# gsm.net
KiCad netlist of a schematic drawn in EAGLE
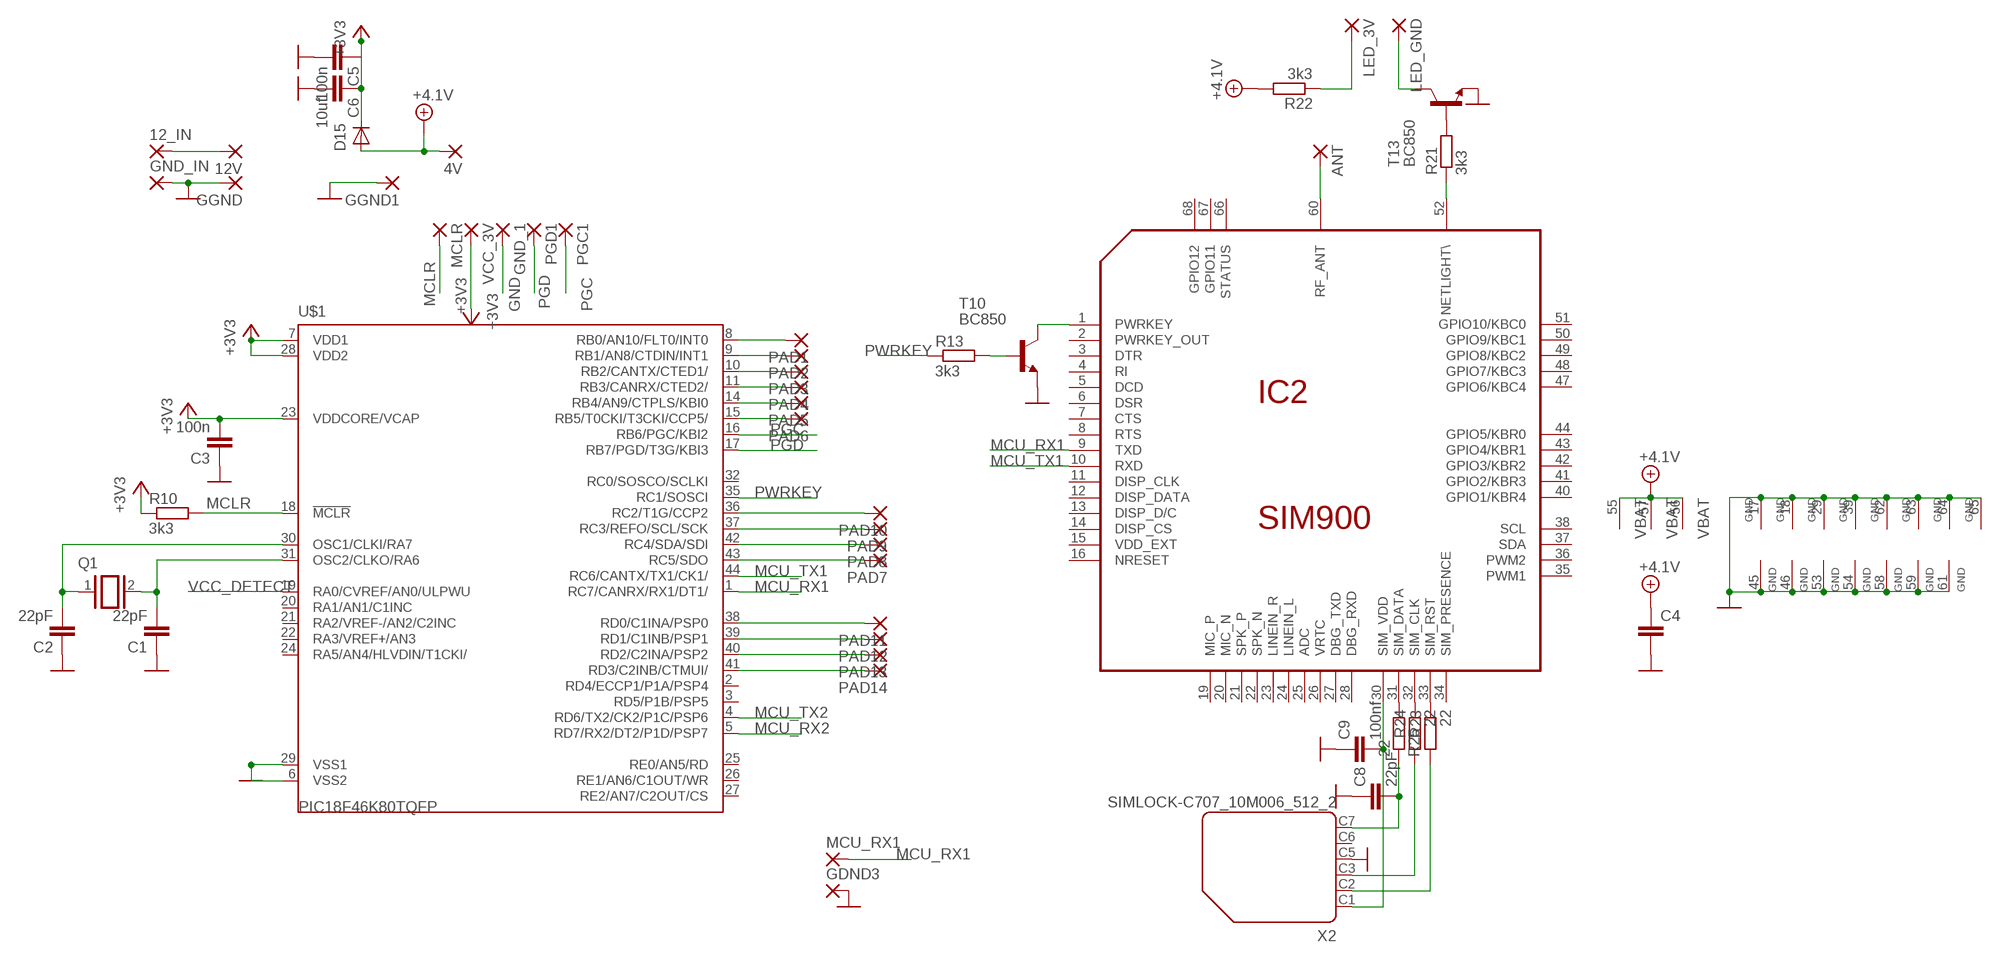
[diagram p0: schematic, sheet 1]

(export (version "E")
  (design (tool "Eeschema 10.0.6"))
  (components
    (comp (ref "4V")
      (value "SMD2")
      (footprint "eagle-import:SMD1,27-2,54")
      (libsource (lib "eagle-import") (part "SMD2"))
    )
    (comp (ref "12V")
      (value "SMD2")
      (footprint "eagle-import:SMD1,27-2,54")
      (libsource (lib "eagle-import") (part "SMD2"))
    )
    (comp (ref "12_IN")
      (value "2,15/1,0")
      (footprint "eagle-import:2,15_1,0")
      (libsource (lib "eagle-import") (part "2,15/1,0"))
    )
    (comp (ref "ANT")
      (value "2,54/0,8")
      (footprint "eagle-import:2,54_0,8")
      (libsource (lib "eagle-import") (part "2,54/0,8"))
    )
    (comp (ref "C1")
      (value "22pF")
      (footprint "eagle-import:C1206")
      (libsource (lib "eagle-import") (part "resistor_C-EUC1206"))
    )
    (comp (ref "C2")
      (value "22pF")
      (footprint "eagle-import:C1206")
      (libsource (lib "eagle-import") (part "resistor_C-EUC1206"))
    )
    (comp (ref "C3")
      (value "100n")
      (footprint "eagle-import:C1206")
      (libsource (lib "eagle-import") (part "resistor_C-EUC1206"))
    )
    (comp (ref "C4")
      (value "C-EU025-050X050")
      (footprint "eagle-import:C025-050X050")
      (libsource (lib "eagle-import") (part "C-EU025-050X050"))
    )
    (comp (ref "C5")
      (value "100n")
      (footprint "eagle-import:C1206")
      (libsource (lib "eagle-import") (part "resistor_C-EUC1206"))
    )
    (comp (ref "C6")
      (value "10uf")
      (footprint "eagle-import:C1206")
      (libsource (lib "eagle-import") (part "resistor_C-EUC1206"))
    )
    (comp (ref "C8")
      (value "22pF")
      (footprint "eagle-import:C1206K")
      (libsource (lib "eagle-import") (part "C-EUC1206K"))
    )
    (comp (ref "C9")
      (value "100nf")
      (footprint "eagle-import:C1206K")
      (libsource (lib "eagle-import") (part "C-EUC1206K"))
    )
    (comp (ref "D15")
      (value "GF1")
      (footprint "eagle-import:SMA-DO214AC")
      (libsource (lib "eagle-import") (part "GF1"))
    )
    (comp (ref "GDND3")
      (value "2,15/1,0")
      (footprint "eagle-import:2,15_1,0")
      (libsource (lib "eagle-import") (part "2,15/1,0"))
    )
    (comp (ref "GGND")
      (value "SMD2")
      (footprint "eagle-import:SMD1,27-2,54")
      (libsource (lib "eagle-import") (part "SMD2"))
    )
    (comp (ref "GGND1")
      (value "SMD2")
      (footprint "eagle-import:SMD1,27-2,54")
      (libsource (lib "eagle-import") (part "SMD2"))
    )
    (comp (ref "GND_1")
      (value "2,15/1,0")
      (footprint "eagle-import:2,15_1,0")
      (libsource (lib "eagle-import") (part "2,15/1,0"))
    )
    (comp (ref "GND_IN")
      (value "2,15/1,0")
      (footprint "eagle-import:2,15_1,0")
      (libsource (lib "eagle-import") (part "2,15/1,0"))
    )
    (comp (ref "IC2")
      (value "SIM900")
      (footprint "eagle-import:SIM900")
      (libsource (lib "eagle-import") (part "SIM900"))
    )
    (comp (ref "LED_3V")
      (value "WIREPAD2,15/1,0")
      (footprint "eagle-import:2,15_1,0")
      (libsource (lib "eagle-import") (part "WIREPAD2,15/1,0"))
    )
    (comp (ref "LED_GND")
      (value "WIREPAD2,15/1,0")
      (footprint "eagle-import:2,15_1,0")
      (libsource (lib "eagle-import") (part "WIREPAD2,15/1,0"))
    )
    (comp (ref "MCLR")
      (value "2,15/1,0")
      (footprint "eagle-import:2,15_1,0")
      (libsource (lib "eagle-import") (part "2,15/1,0"))
    )
    (comp (ref "MCU_RX1")
      (value "2,15/1,0")
      (footprint "eagle-import:2,15_1,0")
      (libsource (lib "eagle-import") (part "2,15/1,0"))
    )
    (comp (ref "PAD1")
      (value "SMD2")
      (footprint "eagle-import:SMD1,27-2,54")
      (libsource (lib "eagle-import") (part "SMD2"))
    )
    (comp (ref "PAD2")
      (value "SMD2")
      (footprint "eagle-import:SMD1,27-2,54")
      (libsource (lib "eagle-import") (part "SMD2"))
    )
    (comp (ref "PAD3")
      (value "SMD2")
      (footprint "eagle-import:SMD1,27-2,54")
      (libsource (lib "eagle-import") (part "SMD2"))
    )
    (comp (ref "PAD4")
      (value "SMD2")
      (footprint "eagle-import:SMD1,27-2,54")
      (libsource (lib "eagle-import") (part "SMD2"))
    )
    (comp (ref "PAD5")
      (value "SMD2")
      (footprint "eagle-import:SMD1,27-2,54")
      (libsource (lib "eagle-import") (part "SMD2"))
    )
    (comp (ref "PAD6")
      (value "SMD2")
      (footprint "eagle-import:SMD1,27-2,54")
      (libsource (lib "eagle-import") (part "SMD2"))
    )
    (comp (ref "PAD7")
      (value "SMD2")
      (footprint "eagle-import:SMD1,27-2,54")
      (libsource (lib "eagle-import") (part "SMD2"))
    )
    (comp (ref "PAD8")
      (value "SMD2")
      (footprint "eagle-import:SMD1,27-2,54")
      (libsource (lib "eagle-import") (part "SMD2"))
    )
    (comp (ref "PAD9")
      (value "SMD2")
      (footprint "eagle-import:SMD1,27-2,54")
      (libsource (lib "eagle-import") (part "SMD2"))
    )
    (comp (ref "PAD10")
      (value "SMD2")
      (footprint "eagle-import:SMD1,27-2,54")
      (libsource (lib "eagle-import") (part "SMD2"))
    )
    (comp (ref "PAD11")
      (value "SMD2")
      (footprint "eagle-import:SMD1,27-2,54")
      (libsource (lib "eagle-import") (part "SMD2"))
    )
    (comp (ref "PAD12")
      (value "SMD2")
      (footprint "eagle-import:SMD1,27-2,54")
      (libsource (lib "eagle-import") (part "SMD2"))
    )
    (comp (ref "PAD13")
      (value "SMD2")
      (footprint "eagle-import:SMD1,27-2,54")
      (libsource (lib "eagle-import") (part "SMD2"))
    )
    (comp (ref "PAD14")
      (value "SMD2")
      (footprint "eagle-import:SMD1,27-2,54")
      (libsource (lib "eagle-import") (part "SMD2"))
    )
    (comp (ref "PGC1")
      (value "2,15/1,0")
      (footprint "eagle-import:2,15_1,0")
      (libsource (lib "eagle-import") (part "2,15/1,0"))
    )
    (comp (ref "PGD1")
      (value "2,15/1,0")
      (footprint "eagle-import:2,15_1,0")
      (libsource (lib "eagle-import") (part "2,15/1,0"))
    )
    (comp (ref "Q1")
      (value "XTAL/S")
      (footprint "eagle-import:QS")
      (libsource (lib "eagle-import") (part "XTAL/S"))
    )
    (comp (ref "R10")
      (value "3k3")
      (footprint "eagle-import:M3216")
      (libsource (lib "eagle-import") (part "R-EU_M3216"))
    )
    (comp (ref "R13")
      (value "3k3")
      (footprint "eagle-import:M3216")
      (libsource (lib "eagle-import") (part "R-EU_M3216"))
    )
    (comp (ref "R21")
      (value "3k3")
      (footprint "eagle-import:M3216")
      (libsource (lib "eagle-import") (part "R-EU_M3216"))
    )
    (comp (ref "R22")
      (value "3k3")
      (footprint "eagle-import:M3216")
      (libsource (lib "eagle-import") (part "R-EU_M3216"))
    )
    (comp (ref "R23")
      (value "22")
      (footprint "eagle-import:M1206")
      (libsource (lib "eagle-import") (part "resistor_R-EU_M1206"))
    )
    (comp (ref "R24")
      (value "22")
      (footprint "eagle-import:M1206")
      (libsource (lib "eagle-import") (part "resistor_R-EU_M1206"))
    )
    (comp (ref "R25")
      (value "22")
      (footprint "eagle-import:M1206")
      (libsource (lib "eagle-import") (part "resistor_R-EU_M1206"))
    )
    (comp (ref "T10")
      (value "BC850")
      (footprint "eagle-import:SOT23")
      (libsource (lib "eagle-import") (part "BC850"))
    )
    (comp (ref "T13")
      (value "BC850")
      (footprint "eagle-import:SOT23")
      (libsource (lib "eagle-import") (part "BC850"))
    )
    (comp (ref "U$1")
      (value "PIC18F46K80TQFP")
      (footprint "eagle-import:TQFP44")
      (libsource (lib "eagle-import") (part "PIC18F46K80TQFP"))
    )
    (comp (ref "VCC_3V")
      (value "2,15/1,0")
      (footprint "eagle-import:2,15_1,0")
      (libsource (lib "eagle-import") (part "2,15/1,0"))
    )
    (comp (ref "X2")
      (value "SIMLOCK-C707_10M006_512_2")
      (footprint "eagle-import:C707_10M006_512_2")
      (libsource (lib "eagle-import") (part "SIMLOCK-C707_10M006_512_2"))
    )
  )
  (nets
    (net (code "1") (name "+3V3") (class "Default")
      (node (ref "C3") (pin "2") (pinfunction "2_2") (pintype "passive"))
      (node (ref "C5") (pin "1") (pinfunction "1_1") (pintype "passive"))
      (node (ref "C6") (pin "1") (pinfunction "1_1") (pintype "passive"))
      (node (ref "D15") (pin "K") (pinfunction "C_K") (pintype "passive"))
      (node (ref "R10") (pin "1") (pinfunction "1_1") (pintype "passive"))
      (node (ref "U$1") (pin "23") (pinfunction "VDDCORE/VCAP_23") (pintype "input"))
      (node (ref "U$1") (pin "28") (pinfunction "VDD2_28") (pintype "input"))
      (node (ref "U$1") (pin "7") (pinfunction "VDD1_7") (pintype "input"))
      (node (ref "VCC_3V") (pin "1") (pinfunction "P_1") (pintype "passive"))
    )
    (net (code "2") (name "+4.1V") (class "Default")
      (node (ref "4V") (pin "1") (pinfunction "P_1") (pintype "passive"))
      (node (ref "C4") (pin "1") (pinfunction "1_1") (pintype "passive"))
      (node (ref "D15") (pin "A") (pinfunction "A_A") (pintype "passive"))
      (node (ref "IC2") (pin "55") (pinfunction "VBAT_55") (pintype "power_in"))
      (node (ref "IC2") (pin "56") (pinfunction "VBAT_56") (pintype "power_in"))
      (node (ref "IC2") (pin "57") (pinfunction "VBAT_57") (pintype "power_in"))
      (node (ref "R22") (pin "2") (pinfunction "2_2") (pintype "passive"))
    )
    (net (code "3") (name "/MCLR") (class "Default")
      (node (ref "MCLR") (pin "1") (pinfunction "P_1") (pintype "passive"))
      (node (ref "R10") (pin "2") (pinfunction "2_2") (pintype "passive"))
      (node (ref "U$1") (pin "18") (pinfunction "~{MCLR}_18") (pintype "input"))
    )
    (net (code "4") (name "/MCU_RX1") (class "Default")
      (node (ref "IC2") (pin "9") (pinfunction "TXD_9") (pintype "bidirectional"))
      (node (ref "MCU_RX1") (pin "1") (pinfunction "P_1") (pintype "passive"))
      (node (ref "U$1") (pin "1") (pinfunction "RC7/CANRX/RX1/DT1/_1") (pintype "bidirectional"))
    )
    (net (code "5") (name "/MCU_RX2") (class "Default")
      (node (ref "U$1") (pin "5") (pinfunction "RD7/RX2/DT2/P1D/PSP7_5") (pintype "bidirectional"))
    )
    (net (code "6") (name "/MCU_TX1") (class "Default")
      (node (ref "IC2") (pin "10") (pinfunction "RXD_10") (pintype "bidirectional"))
      (node (ref "U$1") (pin "44") (pinfunction "RC6/CANTX/TX1/CK1/_44") (pintype "bidirectional"))
    )
    (net (code "7") (name "/MCU_TX2") (class "Default")
      (node (ref "U$1") (pin "4") (pinfunction "RD6/TX2/CK2/P1C/PSP6_4") (pintype "bidirectional"))
    )
    (net (code "8") (name "/PGC") (class "Default")
      (node (ref "PGC1") (pin "1") (pinfunction "P_1") (pintype "passive"))
      (node (ref "U$1") (pin "16") (pinfunction "RB6/PGC/KBI2_16") (pintype "bidirectional"))
    )
    (net (code "9") (name "/PGD") (class "Default")
      (node (ref "PGD1") (pin "1") (pinfunction "P_1") (pintype "passive"))
      (node (ref "U$1") (pin "17") (pinfunction "RB7/PGD/T3G/KBI3_17") (pintype "bidirectional"))
    )
    (net (code "10") (name "/PWRKEY") (class "Default")
      (node (ref "R13") (pin "1") (pinfunction "1_1") (pintype "passive"))
      (node (ref "U$1") (pin "35") (pinfunction "RC1/SOSCI_35") (pintype "bidirectional"))
    )
    (net (code "11") (name "/VCC_DETECT") (class "Default")
      (node (ref "U$1") (pin "19") (pinfunction "RA0/CVREF/AN0/ULPWU_19") (pintype "bidirectional"))
    )
    (net (code "12") (name "GND") (class "Default")
      (node (ref "C1") (pin "1") (pinfunction "1_1") (pintype "passive"))
      (node (ref "C2") (pin "1") (pinfunction "1_1") (pintype "passive"))
      (node (ref "C3") (pin "1") (pinfunction "1_1") (pintype "passive"))
      (node (ref "C4") (pin "2") (pinfunction "2_2") (pintype "passive"))
      (node (ref "C5") (pin "2") (pinfunction "2_2") (pintype "passive"))
      (node (ref "C6") (pin "2") (pinfunction "2_2") (pintype "passive"))
      (node (ref "C8") (pin "1") (pinfunction "1_1") (pintype "passive"))
      (node (ref "C9") (pin "1") (pinfunction "1_1") (pintype "passive"))
      (node (ref "GDND3") (pin "1") (pinfunction "P_1") (pintype "passive"))
      (node (ref "GGND") (pin "1") (pinfunction "P_1") (pintype "passive"))
      (node (ref "GGND1") (pin "1") (pinfunction "P_1") (pintype "passive"))
      (node (ref "GND_1") (pin "1") (pinfunction "P_1") (pintype "passive"))
      (node (ref "GND_IN") (pin "1") (pinfunction "P_1") (pintype "passive"))
      (node (ref "IC2") (pin "17") (pinfunction "GND_17") (pintype "power_in"))
      (node (ref "IC2") (pin "18") (pinfunction "GND_18") (pintype "power_in"))
      (node (ref "IC2") (pin "29") (pinfunction "GND_29") (pintype "power_in"))
      (node (ref "IC2") (pin "39") (pinfunction "GND_39") (pintype "power_in"))
      (node (ref "IC2") (pin "45") (pinfunction "GND_45") (pintype "power_in"))
      (node (ref "IC2") (pin "46") (pinfunction "GND_46") (pintype "power_in"))
      (node (ref "IC2") (pin "53") (pinfunction "GND_53") (pintype "power_in"))
      (node (ref "IC2") (pin "54") (pinfunction "GND_54") (pintype "power_in"))
      (node (ref "IC2") (pin "58") (pinfunction "GND_58") (pintype "power_in"))
      (node (ref "IC2") (pin "59") (pinfunction "GND_59") (pintype "power_in"))
      (node (ref "IC2") (pin "61") (pinfunction "GND_61") (pintype "power_in"))
      (node (ref "IC2") (pin "62") (pinfunction "GND_62") (pintype "power_in"))
      (node (ref "IC2") (pin "63") (pinfunction "GND_63") (pintype "power_in"))
      (node (ref "IC2") (pin "64") (pinfunction "GND_64") (pintype "power_in"))
      (node (ref "IC2") (pin "65") (pinfunction "GND_65") (pintype "power_in"))
      (node (ref "T10") (pin "2") (pinfunction "E_2") (pintype "passive"))
      (node (ref "T13") (pin "2") (pinfunction "E_2") (pintype "passive"))
      (node (ref "U$1") (pin "29") (pinfunction "VSS1_29") (pintype "input"))
      (node (ref "U$1") (pin "6") (pinfunction "VSS2_6") (pintype "input"))
      (node (ref "X2") (pin "C5") (pinfunction "4_C5") (pintype "passive"))
    )
    (net (code "13") (name "Net-(12V-P)") (class "Default")
      (node (ref "12V") (pin "1") (pinfunction "P_1") (pintype "passive"))
      (node (ref "12_IN") (pin "1") (pinfunction "P_1") (pintype "passive"))
    )
    (net (code "14") (name "Net-(ANT-P)") (class "Default")
      (node (ref "ANT") (pin "1") (pinfunction "P_1") (pintype "passive"))
      (node (ref "IC2") (pin "60") (pinfunction "RF_ANT_60") (pintype "bidirectional"))
    )
    (net (code "15") (name "Net-(IC2A-NETLIGHT\\)") (class "Default")
      (node (ref "IC2") (pin "52") (pinfunction "NETLIGHT\\_52") (pintype "bidirectional"))
      (node (ref "R21") (pin "1") (pinfunction "1_1") (pintype "passive"))
    )
    (net (code "16") (name "Net-(IC2A-PWRKEY)") (class "Default")
      (node (ref "IC2") (pin "1") (pinfunction "PWRKEY_1") (pintype "bidirectional"))
      (node (ref "T10") (pin "3") (pinfunction "C_3") (pintype "passive"))
    )
    (net (code "17") (name "Net-(IC2A-SIM_CLK)") (class "Default")
      (node (ref "IC2") (pin "32") (pinfunction "SIM_CLK_32") (pintype "bidirectional"))
      (node (ref "R24") (pin "1") (pinfunction "1_1") (pintype "passive"))
    )
    (net (code "18") (name "Net-(IC2A-SIM_DATA)") (class "Default")
      (node (ref "IC2") (pin "31") (pinfunction "SIM_DATA_31") (pintype "bidirectional"))
      (node (ref "R25") (pin "2") (pinfunction "2_2") (pintype "passive"))
    )
    (net (code "19") (name "Net-(IC2A-SIM_RST)") (class "Default")
      (node (ref "IC2") (pin "33") (pinfunction "SIM_RST_33") (pintype "bidirectional"))
      (node (ref "R23") (pin "1") (pinfunction "1_1") (pintype "passive"))
    )
    (net (code "20") (name "Net-(IC2A-SIM_VDD)") (class "Default")
      (node (ref "C9") (pin "2") (pinfunction "2_2") (pintype "passive"))
      (node (ref "IC2") (pin "30") (pinfunction "SIM_VDD_30") (pintype "bidirectional"))
      (node (ref "X2") (pin "C1") (pinfunction "1_C1") (pintype "passive"))
    )
    (net (code "21") (name "Net-(LED_3V-P)") (class "Default")
      (node (ref "LED_3V") (pin "1") (pinfunction "P_1") (pintype "passive"))
      (node (ref "R22") (pin "1") (pinfunction "1_1") (pintype "passive"))
    )
    (net (code "22") (name "Net-(LED_GND-P)") (class "Default")
      (node (ref "LED_GND") (pin "1") (pinfunction "P_1") (pintype "passive"))
      (node (ref "T13") (pin "3") (pinfunction "C_3") (pintype "passive"))
    )
    (net (code "23") (name "Net-(PAD1-P)") (class "Default")
      (node (ref "PAD1") (pin "1") (pinfunction "P_1") (pintype "passive"))
      (node (ref "U$1") (pin "8") (pinfunction "RB0/AN10/FLT0/INT0_8") (pintype "bidirectional"))
    )
    (net (code "24") (name "Net-(PAD2-P)") (class "Default")
      (node (ref "PAD2") (pin "1") (pinfunction "P_1") (pintype "passive"))
      (node (ref "U$1") (pin "9") (pinfunction "RB1/AN8/CTDIN/INT1_9") (pintype "bidirectional"))
    )
    (net (code "25") (name "Net-(PAD3-P)") (class "Default")
      (node (ref "PAD3") (pin "1") (pinfunction "P_1") (pintype "passive"))
      (node (ref "U$1") (pin "10") (pinfunction "RB2/CANTX/CTED1/_10") (pintype "bidirectional"))
    )
    (net (code "26") (name "Net-(PAD4-P)") (class "Default")
      (node (ref "PAD4") (pin "1") (pinfunction "P_1") (pintype "passive"))
      (node (ref "U$1") (pin "11") (pinfunction "RB3/CANRX/CTED2/_11") (pintype "bidirectional"))
    )
    (net (code "27") (name "Net-(PAD5-P)") (class "Default")
      (node (ref "PAD5") (pin "1") (pinfunction "P_1") (pintype "passive"))
      (node (ref "U$1") (pin "14") (pinfunction "RB4/AN9/CTPLS/KBI0_14") (pintype "bidirectional"))
    )
    (net (code "28") (name "Net-(PAD6-P)") (class "Default")
      (node (ref "PAD6") (pin "1") (pinfunction "P_1") (pintype "passive"))
      (node (ref "U$1") (pin "15") (pinfunction "RB5/T0CKI/T3CKI/CCP5/_15") (pintype "bidirectional"))
    )
    (net (code "29") (name "Net-(PAD7-P)") (class "Default")
      (node (ref "PAD7") (pin "1") (pinfunction "P_1") (pintype "passive"))
      (node (ref "U$1") (pin "43") (pinfunction "RC5/SDO_43") (pintype "bidirectional"))
    )
    (net (code "30") (name "Net-(PAD8-P)") (class "Default")
      (node (ref "PAD8") (pin "1") (pinfunction "P_1") (pintype "passive"))
      (node (ref "U$1") (pin "42") (pinfunction "RC4/SDA/SDI_42") (pintype "bidirectional"))
    )
    (net (code "31") (name "Net-(PAD9-P)") (class "Default")
      (node (ref "PAD9") (pin "1") (pinfunction "P_1") (pintype "passive"))
      (node (ref "U$1") (pin "37") (pinfunction "RC3/REFO/SCL/SCK_37") (pintype "input"))
    )
    (net (code "32") (name "Net-(PAD10-P)") (class "Default")
      (node (ref "PAD10") (pin "1") (pinfunction "P_1") (pintype "passive"))
      (node (ref "U$1") (pin "36") (pinfunction "RC2/T1G/CCP2_36") (pintype "bidirectional"))
    )
    (net (code "33") (name "Net-(PAD11-P)") (class "Default")
      (node (ref "PAD11") (pin "1") (pinfunction "P_1") (pintype "passive"))
      (node (ref "U$1") (pin "38") (pinfunction "RD0/C1INA/PSP0_38") (pintype "bidirectional"))
    )
    (net (code "34") (name "Net-(PAD12-P)") (class "Default")
      (node (ref "PAD12") (pin "1") (pinfunction "P_1") (pintype "passive"))
      (node (ref "U$1") (pin "39") (pinfunction "RD1/C1INB/PSP1_39") (pintype "bidirectional"))
    )
    (net (code "35") (name "Net-(PAD13-P)") (class "Default")
      (node (ref "PAD13") (pin "1") (pinfunction "P_1") (pintype "passive"))
      (node (ref "U$1") (pin "40") (pinfunction "RD2/C2INA/PSP2_40") (pintype "bidirectional"))
    )
    (net (code "36") (name "Net-(PAD14-P)") (class "Default")
      (node (ref "PAD14") (pin "1") (pinfunction "P_1") (pintype "passive"))
      (node (ref "U$1") (pin "41") (pinfunction "RD3/C2INB/CTMUI/_41") (pintype "bidirectional"))
    )
    (net (code "37") (name "Net-(T10-B)") (class "Default")
      (node (ref "R13") (pin "2") (pinfunction "2_2") (pintype "passive"))
      (node (ref "T10") (pin "1") (pinfunction "B_1") (pintype "passive"))
    )
    (net (code "38") (name "Net-(T13-B)") (class "Default")
      (node (ref "R21") (pin "2") (pinfunction "2_2") (pintype "passive"))
      (node (ref "T13") (pin "1") (pinfunction "B_1") (pintype "passive"))
    )
    (net (code "39") (name "Net-(U$1-OSC1{slash}CLKI{slash}RA7)") (class "Default")
      (node (ref "C2") (pin "2") (pinfunction "2_2") (pintype "passive"))
      (node (ref "Q1") (pin "1") (pinfunction "1_1") (pintype "passive"))
      (node (ref "U$1") (pin "30") (pinfunction "OSC1/CLKI/RA7_30") (pintype "bidirectional"))
    )
    (net (code "40") (name "Net-(U$1-OSC2{slash}CLKO{slash}RA6)") (class "Default")
      (node (ref "C1") (pin "2") (pinfunction "2_2") (pintype "passive"))
      (node (ref "Q1") (pin "2") (pinfunction "2_2") (pintype "passive"))
      (node (ref "U$1") (pin "31") (pinfunction "OSC2/CLKO/RA6_31") (pintype "bidirectional"))
    )
    (net (code "41") (name "Net-(X2-2)") (class "Default")
      (node (ref "R23") (pin "2") (pinfunction "2_2") (pintype "passive"))
      (node (ref "X2") (pin "C2") (pinfunction "2_C2") (pintype "passive"))
    )
    (net (code "42") (name "Net-(X2-3)") (class "Default")
      (node (ref "R24") (pin "2") (pinfunction "2_2") (pintype "passive"))
      (node (ref "X2") (pin "C3") (pinfunction "3_C3") (pintype "passive"))
    )
    (net (code "43") (name "Net-(X2-6)") (class "Default")
      (node (ref "C8") (pin "2") (pinfunction "2_2") (pintype "passive"))
      (node (ref "R25") (pin "1") (pinfunction "1_1") (pintype "passive"))
      (node (ref "X2") (pin "C7") (pinfunction "6_C7") (pintype "passive"))
    )
    (net (code "44") (name "unconnected-(IC2A-ADC-Pad25)") (class "Default")
      (node (ref "IC2") (pin "25") (pinfunction "ADC_25") (pintype "bidirectional"))
    )
    (net (code "45") (name "unconnected-(IC2A-CTS-Pad7)") (class "Default")
      (node (ref "IC2") (pin "7") (pinfunction "CTS_7") (pintype "bidirectional"))
    )
    (net (code "46") (name "unconnected-(IC2A-DBG_RXD-Pad28)") (class "Default")
      (node (ref "IC2") (pin "28") (pinfunction "DBG_RXD_28") (pintype "bidirectional"))
    )
    (net (code "47") (name "unconnected-(IC2A-DBG_TXD-Pad27)") (class "Default")
      (node (ref "IC2") (pin "27") (pinfunction "DBG_TXD_27") (pintype "bidirectional"))
    )
    (net (code "48") (name "unconnected-(IC2A-DCD-Pad5)") (class "Default")
      (node (ref "IC2") (pin "5") (pinfunction "DCD_5") (pintype "bidirectional"))
    )
    (net (code "49") (name "unconnected-(IC2A-DISP_CLK-Pad11)") (class "Default")
      (node (ref "IC2") (pin "11") (pinfunction "DISP_CLK_11") (pintype "bidirectional"))
    )
    (net (code "50") (name "unconnected-(IC2A-DISP_CS-Pad14)") (class "Default")
      (node (ref "IC2") (pin "14") (pinfunction "DISP_CS_14") (pintype "bidirectional"))
    )
    (net (code "51") (name "unconnected-(IC2A-DISP_DATA-Pad12)") (class "Default")
      (node (ref "IC2") (pin "12") (pinfunction "DISP_DATA_12") (pintype "bidirectional"))
    )
    (net (code "52") (name "unconnected-(IC2A-DISP_D{slash}C-Pad13)") (class "Default")
      (node (ref "IC2") (pin "13") (pinfunction "DISP_D/C_13") (pintype "bidirectional"))
    )
    (net (code "53") (name "unconnected-(IC2A-DSR-Pad6)") (class "Default")
      (node (ref "IC2") (pin "6") (pinfunction "DSR_6") (pintype "bidirectional"))
    )
    (net (code "54") (name "unconnected-(IC2A-DTR-Pad3)") (class "Default")
      (node (ref "IC2") (pin "3") (pinfunction "DTR_3") (pintype "bidirectional"))
    )
    (net (code "55") (name "unconnected-(IC2A-GPIO1{slash}KBR4-Pad40)") (class "Default")
      (node (ref "IC2") (pin "40") (pinfunction "GPIO1/KBR4_40") (pintype "bidirectional"))
    )
    (net (code "56") (name "unconnected-(IC2A-GPIO2{slash}KBR3-Pad41)") (class "Default")
      (node (ref "IC2") (pin "41") (pinfunction "GPIO2/KBR3_41") (pintype "bidirectional"))
    )
    (net (code "57") (name "unconnected-(IC2A-GPIO3{slash}KBR2-Pad42)") (class "Default")
      (node (ref "IC2") (pin "42") (pinfunction "GPIO3/KBR2_42") (pintype "bidirectional"))
    )
    (net (code "58") (name "unconnected-(IC2A-GPIO4{slash}KBR1-Pad43)") (class "Default")
      (node (ref "IC2") (pin "43") (pinfunction "GPIO4/KBR1_43") (pintype "bidirectional"))
    )
    (net (code "59") (name "unconnected-(IC2A-GPIO5{slash}KBR0-Pad44)") (class "Default")
      (node (ref "IC2") (pin "44") (pinfunction "GPIO5/KBR0_44") (pintype "bidirectional"))
    )
    (net (code "60") (name "unconnected-(IC2A-GPIO6{slash}KBC4-Pad47)") (class "Default")
      (node (ref "IC2") (pin "47") (pinfunction "GPIO6/KBC4_47") (pintype "bidirectional"))
    )
    (net (code "61") (name "unconnected-(IC2A-GPIO7{slash}KBC3-Pad48)") (class "Default")
      (node (ref "IC2") (pin "48") (pinfunction "GPIO7/KBC3_48") (pintype "bidirectional"))
    )
    (net (code "62") (name "unconnected-(IC2A-GPIO8{slash}KBC2-Pad49)") (class "Default")
      (node (ref "IC2") (pin "49") (pinfunction "GPIO8/KBC2_49") (pintype "bidirectional"))
    )
    (net (code "63") (name "unconnected-(IC2A-GPIO9{slash}KBC1-Pad50)") (class "Default")
      (node (ref "IC2") (pin "50") (pinfunction "GPIO9/KBC1_50") (pintype "bidirectional"))
    )
    (net (code "64") (name "unconnected-(IC2A-GPIO10{slash}KBC0-Pad51)") (class "Default")
      (node (ref "IC2") (pin "51") (pinfunction "GPIO10/KBC0_51") (pintype "bidirectional"))
    )
    (net (code "65") (name "unconnected-(IC2A-GPIO11-Pad67)") (class "Default")
      (node (ref "IC2") (pin "67") (pinfunction "GPIO11_67") (pintype "bidirectional"))
    )
    (net (code "66") (name "unconnected-(IC2A-GPIO12-Pad68)") (class "Default")
      (node (ref "IC2") (pin "68") (pinfunction "GPIO12_68") (pintype "bidirectional"))
    )
    (net (code "67") (name "unconnected-(IC2A-LINEIN_L-Pad24)") (class "Default")
      (node (ref "IC2") (pin "24") (pinfunction "LINEIN_L_24") (pintype "bidirectional"))
    )
    (net (code "68") (name "unconnected-(IC2A-LINEIN_R-Pad23)") (class "Default")
      (node (ref "IC2") (pin "23") (pinfunction "LINEIN_R_23") (pintype "bidirectional"))
    )
    (net (code "69") (name "unconnected-(IC2A-MIC_N-Pad20)") (class "Default")
      (node (ref "IC2") (pin "20") (pinfunction "MIC_N_20") (pintype "bidirectional"))
    )
    (net (code "70") (name "unconnected-(IC2A-MIC_P-Pad19)") (class "Default")
      (node (ref "IC2") (pin "19") (pinfunction "MIC_P_19") (pintype "bidirectional"))
    )
    (net (code "71") (name "unconnected-(IC2A-NRESET-Pad16)") (class "Default")
      (node (ref "IC2") (pin "16") (pinfunction "NRESET_16") (pintype "bidirectional"))
    )
    (net (code "72") (name "unconnected-(IC2A-PWM1-Pad35)") (class "Default")
      (node (ref "IC2") (pin "35") (pinfunction "PWM1_35") (pintype "bidirectional"))
    )
    (net (code "73") (name "unconnected-(IC2A-PWM2-Pad36)") (class "Default")
      (node (ref "IC2") (pin "36") (pinfunction "PWM2_36") (pintype "bidirectional"))
    )
    (net (code "74") (name "unconnected-(IC2A-PWRKEY_OUT-Pad2)") (class "Default")
      (node (ref "IC2") (pin "2") (pinfunction "PWRKEY_OUT_2") (pintype "bidirectional"))
    )
    (net (code "75") (name "unconnected-(IC2A-RI-Pad4)") (class "Default")
      (node (ref "IC2") (pin "4") (pinfunction "RI_4") (pintype "bidirectional"))
    )
    (net (code "76") (name "unconnected-(IC2A-RTS-Pad8)") (class "Default")
      (node (ref "IC2") (pin "8") (pinfunction "RTS_8") (pintype "bidirectional"))
    )
    (net (code "77") (name "unconnected-(IC2A-SCL-Pad38)") (class "Default")
      (node (ref "IC2") (pin "38") (pinfunction "SCL_38") (pintype "bidirectional"))
    )
    (net (code "78") (name "unconnected-(IC2A-SDA-Pad37)") (class "Default")
      (node (ref "IC2") (pin "37") (pinfunction "SDA_37") (pintype "bidirectional"))
    )
    (net (code "79") (name "unconnected-(IC2A-SIM_PRESENCE-Pad34)") (class "Default")
      (node (ref "IC2") (pin "34") (pinfunction "SIM_PRESENCE_34") (pintype "bidirectional"))
    )
    (net (code "80") (name "unconnected-(IC2A-SPK_N-Pad22)") (class "Default")
      (node (ref "IC2") (pin "22") (pinfunction "SPK_N_22") (pintype "bidirectional"))
    )
    (net (code "81") (name "unconnected-(IC2A-SPK_P-Pad21)") (class "Default")
      (node (ref "IC2") (pin "21") (pinfunction "SPK_P_21") (pintype "bidirectional"))
    )
    (net (code "82") (name "unconnected-(IC2A-STATUS-Pad66)") (class "Default")
      (node (ref "IC2") (pin "66") (pinfunction "STATUS_66") (pintype "bidirectional"))
    )
    (net (code "83") (name "unconnected-(IC2A-VDD_EXT-Pad15)") (class "Default")
      (node (ref "IC2") (pin "15") (pinfunction "VDD_EXT_15") (pintype "bidirectional"))
    )
    (net (code "84") (name "unconnected-(IC2A-VRTC-Pad26)") (class "Default")
      (node (ref "IC2") (pin "26") (pinfunction "VRTC_26") (pintype "bidirectional"))
    )
    (net (code "85") (name "unconnected-(U$1-RA1{slash}AN1{slash}C1INC-Pad20)") (class "Default")
      (node (ref "U$1") (pin "20") (pinfunction "RA1/AN1/C1INC_20") (pintype "bidirectional"))
    )
    (net (code "86") (name "unconnected-(U$1-RA2{slash}VREF-{slash}AN2{slash}C2INC-Pad21)") (class "Default")
      (node (ref "U$1") (pin "21") (pinfunction "RA2/VREF-/AN2/C2INC_21") (pintype "bidirectional"))
    )
    (net (code "87") (name "unconnected-(U$1-RA3{slash}VREF+{slash}AN3-Pad22)") (class "Default")
      (node (ref "U$1") (pin "22") (pinfunction "RA3/VREF+/AN3_22") (pintype "bidirectional"))
    )
    (net (code "88") (name "unconnected-(U$1-RA5{slash}AN4{slash}HLVDIN{slash}T1CKI{slash}-Pad24)") (class "Default")
      (node (ref "U$1") (pin "24") (pinfunction "RA5/AN4/HLVDIN/T1CKI/_24") (pintype "bidirectional"))
    )
    (net (code "89") (name "unconnected-(U$1-RC0{slash}SOSCO{slash}SCLKI-Pad32)") (class "Default")
      (node (ref "U$1") (pin "32") (pinfunction "RC0/SOSCO/SCLKI_32") (pintype "bidirectional"))
    )
    (net (code "90") (name "unconnected-(U$1-RD4{slash}ECCP1{slash}P1A{slash}PSP4-Pad2)") (class "Default")
      (node (ref "U$1") (pin "2") (pinfunction "RD4/ECCP1/P1A/PSP4_2") (pintype "bidirectional"))
    )
    (net (code "91") (name "unconnected-(U$1-RD5{slash}P1B{slash}PSP5-Pad3)") (class "Default")
      (node (ref "U$1") (pin "3") (pinfunction "RD5/P1B/PSP5_3") (pintype "bidirectional"))
    )
    (net (code "92") (name "unconnected-(U$1-RE0{slash}AN5{slash}RD-Pad25)") (class "Default")
      (node (ref "U$1") (pin "25") (pinfunction "RE0/AN5/RD_25") (pintype "bidirectional"))
    )
    (net (code "93") (name "unconnected-(U$1-RE1{slash}AN6{slash}C1OUT{slash}WR-Pad26)") (class "Default")
      (node (ref "U$1") (pin "26") (pinfunction "RE1/AN6/C1OUT/WR_26") (pintype "bidirectional"))
    )
    (net (code "94") (name "unconnected-(U$1-RE2{slash}AN7{slash}C2OUT{slash}CS-Pad27)") (class "Default")
      (node (ref "U$1") (pin "27") (pinfunction "RE2/AN7/C2OUT/CS_27") (pintype "bidirectional"))
    )
    (net (code "95") (name "unconnected-(X2-5-PadC6)") (class "Default")
      (node (ref "X2") (pin "C6") (pinfunction "5_C6") (pintype "passive"))
    )
  )
)
